# eletric.net
KiCad netlist of a schematic drawn in EAGLE
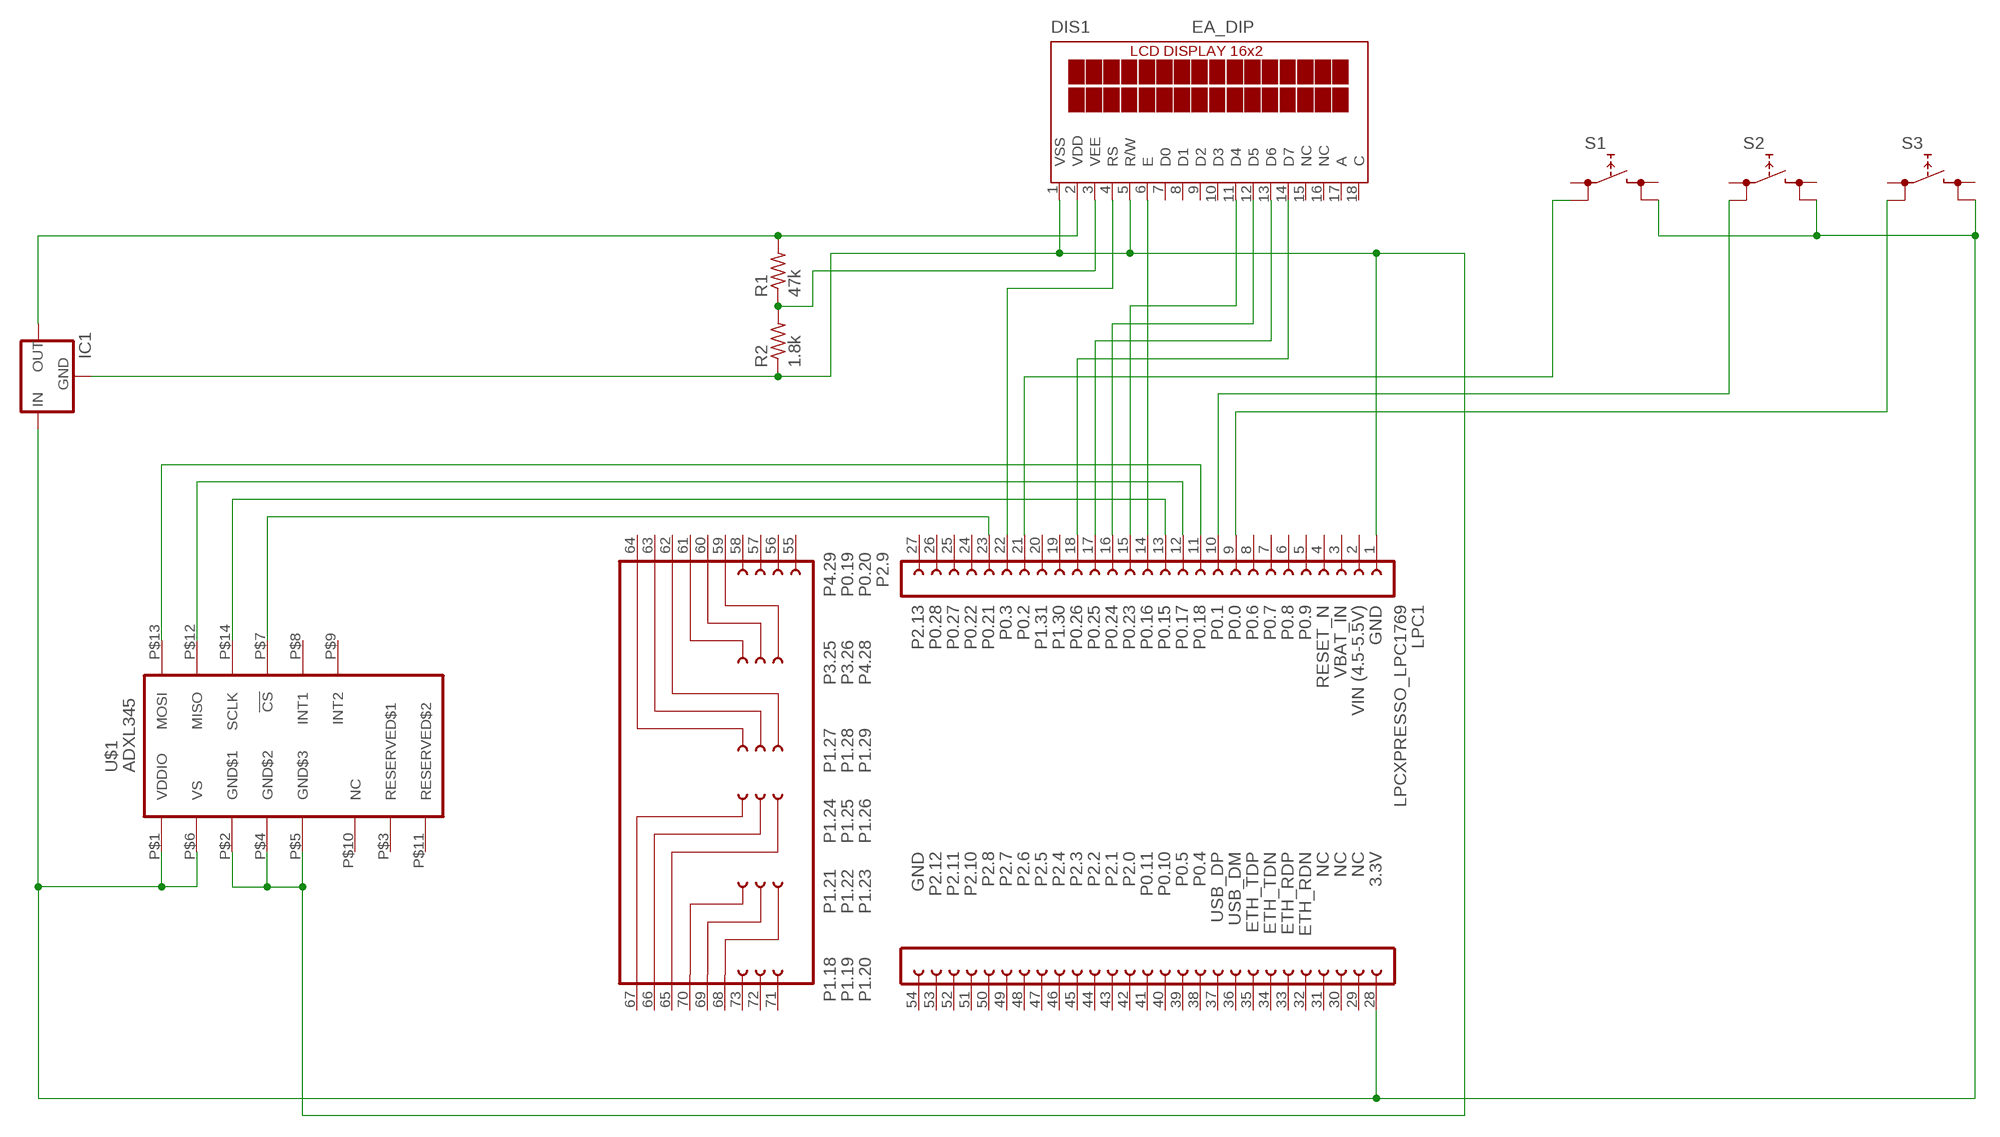
[diagram p0: schematic, sheet 1]

(export (version "E")
  (design (tool "Eeschema 10.0.6"))
  (components
    (comp (ref "DIS1")
      (value "EA_DIP")
      (footprint "eagle-import:EA_DIP")
      (libsource (lib "eagle-import") (part "EA_DIP"))
    )
    (comp (ref "IC1")
      (value "78MXXL")
      (footprint "eagle-import:78MXXL")
      (libsource (lib "eagle-import") (part "78MXXL"))
    )
    (comp (ref "LPC1")
      (value "LPCXPRESSO_LPC1769")
      (footprint "eagle-import:LPCXPRESSO_LPC1769")
      (fields (field (name "MF") "Embedded Artists") (field (name "MP") "LPCXPRESSO LPC1769"))
      (libsource (lib "eagle-import") (part "LPCXPRESSO_LPC1769"))
    )
    (comp (ref "R1")
      (value "47k")
      (footprint "eagle-import:0204V")
      (libsource (lib "eagle-import") (part "R-US_0204/2V"))
    )
    (comp (ref "R2")
      (value "1.8k")
      (footprint "eagle-import:0204V")
      (libsource (lib "eagle-import") (part "R-US_0204/2V"))
    )
    (comp (ref "S1")
      (value "REKN")
      (footprint "eagle-import:REKN")
      (libsource (lib "eagle-import") (part "REKN"))
    )
    (comp (ref "S2")
      (value "REKN")
      (footprint "eagle-import:REKN")
      (libsource (lib "eagle-import") (part "REKN"))
    )
    (comp (ref "S3")
      (value "REKN")
      (footprint "eagle-import:REKN")
      (libsource (lib "eagle-import") (part "REKN"))
    )
    (comp (ref "U$1")
      (value "ADXL345")
      (footprint "eagle-import:LGA14")
      (libsource (lib "eagle-import") (part "ADXL345"))
    )
  )
  (nets
    (net (code "1") (name "Net-(DIS1-D4)") (class "Default")
      (node (ref "DIS1") (pin "11") (pinfunction "D4_11") (pintype "input"))
      (node (ref "LPC1") (pin "15") (pinfunction "15_15") (pintype "passive"))
    )
    (net (code "2") (name "Net-(DIS1-D5)") (class "Default")
      (node (ref "DIS1") (pin "12") (pinfunction "D5_12") (pintype "input"))
      (node (ref "LPC1") (pin "16") (pinfunction "16_16") (pintype "passive"))
    )
    (net (code "3") (name "Net-(DIS1-D6)") (class "Default")
      (node (ref "DIS1") (pin "13") (pinfunction "D6_13") (pintype "input"))
      (node (ref "LPC1") (pin "17") (pinfunction "17_17") (pintype "passive"))
    )
    (net (code "4") (name "Net-(DIS1-D7)") (class "Default")
      (node (ref "DIS1") (pin "14") (pinfunction "D7_14") (pintype "input"))
      (node (ref "LPC1") (pin "18") (pinfunction "18_18") (pintype "passive"))
    )
    (net (code "5") (name "Net-(DIS1-E)") (class "Default")
      (node (ref "DIS1") (pin "6") (pinfunction "E_6") (pintype "input"))
      (node (ref "LPC1") (pin "14") (pinfunction "14_14") (pintype "passive"))
    )
    (net (code "6") (name "Net-(DIS1-RS)") (class "Default")
      (node (ref "DIS1") (pin "4") (pinfunction "RS_4") (pintype "input"))
      (node (ref "LPC1") (pin "22") (pinfunction "22_22") (pintype "passive"))
    )
    (net (code "7") (name "Net-(DIS1-R{slash}W)") (class "Default")
      (node (ref "DIS1") (pin "1") (pinfunction "VSS_1") (pintype "power_in"))
      (node (ref "DIS1") (pin "5") (pinfunction "R/W_5") (pintype "input"))
      (node (ref "IC1") (pin "GND") (pinfunction "GND_GND") (pintype "input"))
      (node (ref "LPC1") (pin "1") (pinfunction "1_1") (pintype "passive"))
      (node (ref "R2") (pin "1") (pinfunction "1_1") (pintype "passive"))
      (node (ref "U$1") (pin "P$2") (pinfunction "GND$1_P$2") (pintype "power_in"))
      (node (ref "U$1") (pin "P$4") (pinfunction "GND$2_P$4") (pintype "power_in"))
      (node (ref "U$1") (pin "P$5") (pinfunction "GND$3_P$5") (pintype "power_in"))
    )
    (net (code "8") (name "Net-(DIS1-VDD)") (class "Default")
      (node (ref "DIS1") (pin "2") (pinfunction "VDD_2") (pintype "power_in"))
      (node (ref "IC1") (pin "OUT") (pinfunction "OUT_OUT") (pintype "passive"))
      (node (ref "R1") (pin "2") (pinfunction "2_2") (pintype "passive"))
    )
    (net (code "9") (name "Net-(DIS1-VEE)") (class "Default")
      (node (ref "DIS1") (pin "3") (pinfunction "VEE_3") (pintype "power_in"))
      (node (ref "R1") (pin "1") (pinfunction "1_1") (pintype "passive"))
      (node (ref "R2") (pin "2") (pinfunction "2_2") (pintype "passive"))
    )
    (net (code "10") (name "Net-(LPC1-Pad9)") (class "Default")
      (node (ref "LPC1") (pin "9") (pinfunction "9_9") (pintype "passive"))
      (node (ref "S3") (pin "0B") (pinfunction "0_0B") (pintype "passive"))
    )
    (net (code "11") (name "Net-(LPC1-Pad10)") (class "Default")
      (node (ref "LPC1") (pin "10") (pinfunction "10_10") (pintype "passive"))
      (node (ref "S2") (pin "0B") (pinfunction "0_0B") (pintype "passive"))
    )
    (net (code "12") (name "Net-(LPC1-Pad21)") (class "Default")
      (node (ref "LPC1") (pin "21") (pinfunction "21_21") (pintype "passive"))
      (node (ref "S1") (pin "0B") (pinfunction "0_0B") (pintype "passive"))
    )
    (net (code "13") (name "Net-(U$1-MISO)") (class "Default")
      (node (ref "LPC1") (pin "12") (pinfunction "12_12") (pintype "passive"))
      (node (ref "U$1") (pin "P$12") (pinfunction "MISO_P$12") (pintype "output"))
    )
    (net (code "14") (name "Net-(U$1-MOSI)") (class "Default")
      (node (ref "LPC1") (pin "11") (pinfunction "11_11") (pintype "passive"))
      (node (ref "U$1") (pin "P$13") (pinfunction "MOSI_P$13") (pintype "input"))
    )
    (net (code "15") (name "Net-(U$1-SCLK)") (class "Default")
      (node (ref "LPC1") (pin "13") (pinfunction "13_13") (pintype "passive"))
      (node (ref "U$1") (pin "P$14") (pinfunction "SCLK_P$14") (pintype "input"))
    )
    (net (code "16") (name "Net-(U$1-VDDIO)") (class "Default")
      (node (ref "IC1") (pin "IN") (pinfunction "IN_IN") (pintype "input"))
      (node (ref "LPC1") (pin "28") (pinfunction "28_28") (pintype "passive"))
      (node (ref "S1") (pin "1B") (pinfunction "1_1B") (pintype "passive"))
      (node (ref "S2") (pin "1B") (pinfunction "1_1B") (pintype "passive"))
      (node (ref "S3") (pin "1B") (pinfunction "1_1B") (pintype "passive"))
      (node (ref "U$1") (pin "P$1") (pinfunction "VDDIO_P$1") (pintype "power_in"))
      (node (ref "U$1") (pin "P$6") (pinfunction "VS_P$6") (pintype "power_in"))
    )
    (net (code "17") (name "Net-(U$1-~{CS})") (class "Default")
      (node (ref "LPC1") (pin "23") (pinfunction "23_23") (pintype "passive"))
      (node (ref "U$1") (pin "P$7") (pinfunction "~{CS}_P$7") (pintype "input"))
    )
    (net (code "18") (name "unconnected-(DIS1-A-Pad17)") (class "Default")
      (node (ref "DIS1") (pin "17") (pinfunction "A_17") (pintype "passive"))
    )
    (net (code "19") (name "unconnected-(DIS1-C-Pad18)") (class "Default")
      (node (ref "DIS1") (pin "18") (pinfunction "C_18") (pintype "passive"))
    )
    (net (code "20") (name "unconnected-(DIS1-D0-Pad7)") (class "Default")
      (node (ref "DIS1") (pin "7") (pinfunction "D0_7") (pintype "input"))
    )
    (net (code "21") (name "unconnected-(DIS1-D1-Pad8)") (class "Default")
      (node (ref "DIS1") (pin "8") (pinfunction "D1_8") (pintype "input"))
    )
    (net (code "22") (name "unconnected-(DIS1-D2-Pad9)") (class "Default")
      (node (ref "DIS1") (pin "9") (pinfunction "D2_9") (pintype "input"))
    )
    (net (code "23") (name "unconnected-(DIS1-D3-Pad10)") (class "Default")
      (node (ref "DIS1") (pin "10") (pinfunction "D3_10") (pintype "input"))
    )
    (net (code "24") (name "unconnected-(DIS1-NC-Pad15)") (class "Default")
      (node (ref "DIS1") (pin "15") (pinfunction "NC_15") (pintype "no_connect"))
    )
    (net (code "25") (name "unconnected-(DIS1-NC-Pad16)") (class "Default")
      (node (ref "DIS1") (pin "16") (pinfunction "NC_16") (pintype "no_connect"))
    )
    (net (code "26") (name "unconnected-(LPC1-Pad2)") (class "Default")
      (node (ref "LPC1") (pin "2") (pinfunction "2_2") (pintype "passive"))
    )
    (net (code "27") (name "unconnected-(LPC1-Pad3)") (class "Default")
      (node (ref "LPC1") (pin "3") (pinfunction "3_3") (pintype "passive"))
    )
    (net (code "28") (name "unconnected-(LPC1-Pad4)") (class "Default")
      (node (ref "LPC1") (pin "4") (pinfunction "4_4") (pintype "passive"))
    )
    (net (code "29") (name "unconnected-(LPC1-Pad5)") (class "Default")
      (node (ref "LPC1") (pin "5") (pinfunction "5_5") (pintype "passive"))
    )
    (net (code "30") (name "unconnected-(LPC1-Pad6)") (class "Default")
      (node (ref "LPC1") (pin "6") (pinfunction "6_6") (pintype "passive"))
    )
    (net (code "31") (name "unconnected-(LPC1-Pad7)") (class "Default")
      (node (ref "LPC1") (pin "7") (pinfunction "7_7") (pintype "passive"))
    )
    (net (code "32") (name "unconnected-(LPC1-Pad8)") (class "Default")
      (node (ref "LPC1") (pin "8") (pinfunction "8_8") (pintype "passive"))
    )
    (net (code "33") (name "unconnected-(LPC1-Pad19)") (class "Default")
      (node (ref "LPC1") (pin "19") (pinfunction "19_19") (pintype "passive"))
    )
    (net (code "34") (name "unconnected-(LPC1-Pad20)") (class "Default")
      (node (ref "LPC1") (pin "20") (pinfunction "20_20") (pintype "passive"))
    )
    (net (code "35") (name "unconnected-(LPC1-Pad24)") (class "Default")
      (node (ref "LPC1") (pin "24") (pinfunction "24_24") (pintype "passive"))
    )
    (net (code "36") (name "unconnected-(LPC1-Pad25)") (class "Default")
      (node (ref "LPC1") (pin "25") (pinfunction "25_25") (pintype "passive"))
    )
    (net (code "37") (name "unconnected-(LPC1-Pad26)") (class "Default")
      (node (ref "LPC1") (pin "26") (pinfunction "26_26") (pintype "passive"))
    )
    (net (code "38") (name "unconnected-(LPC1-Pad27)") (class "Default")
      (node (ref "LPC1") (pin "27") (pinfunction "27_27") (pintype "passive"))
    )
    (net (code "39") (name "unconnected-(LPC1-Pad29)") (class "Default")
      (node (ref "LPC1") (pin "29") (pinfunction "29_29") (pintype "passive"))
    )
    (net (code "40") (name "unconnected-(LPC1-Pad30)") (class "Default")
      (node (ref "LPC1") (pin "30") (pinfunction "30_30") (pintype "passive"))
    )
    (net (code "41") (name "unconnected-(LPC1-Pad31)") (class "Default")
      (node (ref "LPC1") (pin "31") (pinfunction "31_31") (pintype "passive"))
    )
    (net (code "42") (name "unconnected-(LPC1-Pad32)") (class "Default")
      (node (ref "LPC1") (pin "32") (pinfunction "32_32") (pintype "passive"))
    )
    (net (code "43") (name "unconnected-(LPC1-Pad33)") (class "Default")
      (node (ref "LPC1") (pin "33") (pinfunction "33_33") (pintype "passive"))
    )
    (net (code "44") (name "unconnected-(LPC1-Pad34)") (class "Default")
      (node (ref "LPC1") (pin "34") (pinfunction "34_34") (pintype "passive"))
    )
    (net (code "45") (name "unconnected-(LPC1-Pad35)") (class "Default")
      (node (ref "LPC1") (pin "35") (pinfunction "35_35") (pintype "passive"))
    )
    (net (code "46") (name "unconnected-(LPC1-Pad36)") (class "Default")
      (node (ref "LPC1") (pin "36") (pinfunction "36_36") (pintype "passive"))
    )
    (net (code "47") (name "unconnected-(LPC1-Pad37)") (class "Default")
      (node (ref "LPC1") (pin "37") (pinfunction "37_37") (pintype "passive"))
    )
    (net (code "48") (name "unconnected-(LPC1-Pad38)") (class "Default")
      (node (ref "LPC1") (pin "38") (pinfunction "38_38") (pintype "passive"))
    )
    (net (code "49") (name "unconnected-(LPC1-Pad39)") (class "Default")
      (node (ref "LPC1") (pin "39") (pinfunction "39_39") (pintype "passive"))
    )
    (net (code "50") (name "unconnected-(LPC1-Pad40)") (class "Default")
      (node (ref "LPC1") (pin "40") (pinfunction "40_40") (pintype "passive"))
    )
    (net (code "51") (name "unconnected-(LPC1-Pad41)") (class "Default")
      (node (ref "LPC1") (pin "41") (pinfunction "41_41") (pintype "passive"))
    )
    (net (code "52") (name "unconnected-(LPC1-Pad42)") (class "Default")
      (node (ref "LPC1") (pin "42") (pinfunction "42_42") (pintype "passive"))
    )
    (net (code "53") (name "unconnected-(LPC1-Pad43)") (class "Default")
      (node (ref "LPC1") (pin "43") (pinfunction "43_43") (pintype "passive"))
    )
    (net (code "54") (name "unconnected-(LPC1-Pad44)") (class "Default")
      (node (ref "LPC1") (pin "44") (pinfunction "44_44") (pintype "passive"))
    )
    (net (code "55") (name "unconnected-(LPC1-Pad45)") (class "Default")
      (node (ref "LPC1") (pin "45") (pinfunction "45_45") (pintype "passive"))
    )
    (net (code "56") (name "unconnected-(LPC1-Pad46)") (class "Default")
      (node (ref "LPC1") (pin "46") (pinfunction "46_46") (pintype "passive"))
    )
    (net (code "57") (name "unconnected-(LPC1-Pad47)") (class "Default")
      (node (ref "LPC1") (pin "47") (pinfunction "47_47") (pintype "passive"))
    )
    (net (code "58") (name "unconnected-(LPC1-Pad48)") (class "Default")
      (node (ref "LPC1") (pin "48") (pinfunction "48_48") (pintype "passive"))
    )
    (net (code "59") (name "unconnected-(LPC1-Pad49)") (class "Default")
      (node (ref "LPC1") (pin "49") (pinfunction "49_49") (pintype "passive"))
    )
    (net (code "60") (name "unconnected-(LPC1-Pad50)") (class "Default")
      (node (ref "LPC1") (pin "50") (pinfunction "50_50") (pintype "passive"))
    )
    (net (code "61") (name "unconnected-(LPC1-Pad51)") (class "Default")
      (node (ref "LPC1") (pin "51") (pinfunction "51_51") (pintype "passive"))
    )
    (net (code "62") (name "unconnected-(LPC1-Pad52)") (class "Default")
      (node (ref "LPC1") (pin "52") (pinfunction "52_52") (pintype "passive"))
    )
    (net (code "63") (name "unconnected-(LPC1-Pad53)") (class "Default")
      (node (ref "LPC1") (pin "53") (pinfunction "53_53") (pintype "passive"))
    )
    (net (code "64") (name "unconnected-(LPC1-Pad54)") (class "Default")
      (node (ref "LPC1") (pin "54") (pinfunction "54_54") (pintype "passive"))
    )
    (net (code "65") (name "unconnected-(LPC1-Pad55)") (class "Default")
      (node (ref "LPC1") (pin "55") (pinfunction "55_55") (pintype "passive"))
    )
    (net (code "66") (name "unconnected-(LPC1-Pad56)") (class "Default")
      (node (ref "LPC1") (pin "56") (pinfunction "56_56") (pintype "passive"))
    )
    (net (code "67") (name "unconnected-(LPC1-Pad57)") (class "Default")
      (node (ref "LPC1") (pin "57") (pinfunction "57_57") (pintype "passive"))
    )
    (net (code "68") (name "unconnected-(LPC1-Pad58)") (class "Default")
      (node (ref "LPC1") (pin "58") (pinfunction "58_58") (pintype "passive"))
    )
    (net (code "69") (name "unconnected-(LPC1-Pad59)") (class "Default")
      (node (ref "LPC1") (pin "59") (pinfunction "59_59") (pintype "passive"))
    )
    (net (code "70") (name "unconnected-(LPC1-Pad60)") (class "Default")
      (node (ref "LPC1") (pin "60") (pinfunction "60_60") (pintype "passive"))
    )
    (net (code "71") (name "unconnected-(LPC1-Pad61)") (class "Default")
      (node (ref "LPC1") (pin "61") (pinfunction "61_61") (pintype "passive"))
    )
    (net (code "72") (name "unconnected-(LPC1-Pad62)") (class "Default")
      (node (ref "LPC1") (pin "62") (pinfunction "62_62") (pintype "passive"))
    )
    (net (code "73") (name "unconnected-(LPC1-Pad63)") (class "Default")
      (node (ref "LPC1") (pin "63") (pinfunction "63_63") (pintype "passive"))
    )
    (net (code "74") (name "unconnected-(LPC1-Pad64)") (class "Default")
      (node (ref "LPC1") (pin "64") (pinfunction "64_64") (pintype "passive"))
    )
    (net (code "75") (name "unconnected-(LPC1-Pad65)") (class "Default")
      (node (ref "LPC1") (pin "65") (pinfunction "65_65") (pintype "passive"))
    )
    (net (code "76") (name "unconnected-(LPC1-Pad66)") (class "Default")
      (node (ref "LPC1") (pin "66") (pinfunction "66_66") (pintype "passive"))
    )
    (net (code "77") (name "unconnected-(LPC1-Pad67)") (class "Default")
      (node (ref "LPC1") (pin "67") (pinfunction "67_67") (pintype "passive"))
    )
    (net (code "78") (name "unconnected-(LPC1-Pad68)") (class "Default")
      (node (ref "LPC1") (pin "68") (pinfunction "68_68") (pintype "passive"))
    )
    (net (code "79") (name "unconnected-(LPC1-Pad69)") (class "Default")
      (node (ref "LPC1") (pin "69") (pinfunction "69_69") (pintype "passive"))
    )
    (net (code "80") (name "unconnected-(LPC1-Pad70)") (class "Default")
      (node (ref "LPC1") (pin "70") (pinfunction "70_70") (pintype "passive"))
    )
    (net (code "81") (name "unconnected-(LPC1-Pad71)") (class "Default")
      (node (ref "LPC1") (pin "71") (pinfunction "71_71") (pintype "passive"))
    )
    (net (code "82") (name "unconnected-(LPC1-Pad72)") (class "Default")
      (node (ref "LPC1") (pin "72") (pinfunction "72_72") (pintype "passive"))
    )
    (net (code "83") (name "unconnected-(LPC1-Pad73)") (class "Default")
      (node (ref "LPC1") (pin "73") (pinfunction "73_73") (pintype "passive"))
    )
    (net (code "84") (name "unconnected-(S1-0-Pad0A)") (class "Default")
      (node (ref "S1") (pin "0A") (pinfunction "0_0A") (pintype "passive"))
    )
    (net (code "85") (name "unconnected-(S1-1-Pad1A)") (class "Default")
      (node (ref "S1") (pin "1A") (pinfunction "1_1A") (pintype "passive"))
    )
    (net (code "86") (name "unconnected-(S2-0-Pad0A)") (class "Default")
      (node (ref "S2") (pin "0A") (pinfunction "0_0A") (pintype "passive"))
    )
    (net (code "87") (name "unconnected-(S2-1-Pad1A)") (class "Default")
      (node (ref "S2") (pin "1A") (pinfunction "1_1A") (pintype "passive"))
    )
    (net (code "88") (name "unconnected-(S3-0-Pad0A)") (class "Default")
      (node (ref "S3") (pin "0A") (pinfunction "0_0A") (pintype "passive"))
    )
    (net (code "89") (name "unconnected-(S3-1-Pad1A)") (class "Default")
      (node (ref "S3") (pin "1A") (pinfunction "1_1A") (pintype "passive"))
    )
    (net (code "90") (name "unconnected-(U$1-INT1-PadP$8)") (class "Default")
      (node (ref "U$1") (pin "P$8") (pinfunction "INT1_P$8") (pintype "output"))
    )
    (net (code "91") (name "unconnected-(U$1-INT2-PadP$9)") (class "Default")
      (node (ref "U$1") (pin "P$9") (pinfunction "INT2_P$9") (pintype "output"))
    )
    (net (code "92") (name "unconnected-(U$1-NC-PadP$10)") (class "Default")
      (node (ref "U$1") (pin "P$10") (pinfunction "NC_P$10") (pintype "bidirectional"))
    )
    (net (code "93") (name "unconnected-(U$1-RESERVED$1-PadP$3)") (class "Default")
      (node (ref "U$1") (pin "P$3") (pinfunction "RESERVED$1_P$3") (pintype "bidirectional"))
    )
    (net (code "94") (name "unconnected-(U$1-RESERVED$2-PadP$11)") (class "Default")
      (node (ref "U$1") (pin "P$11") (pinfunction "RESERVED$2_P$11") (pintype "bidirectional"))
    )
  )
)
